# Sheet1_Young.net
KiCad netlist of a schematic drawn in Altium Designer
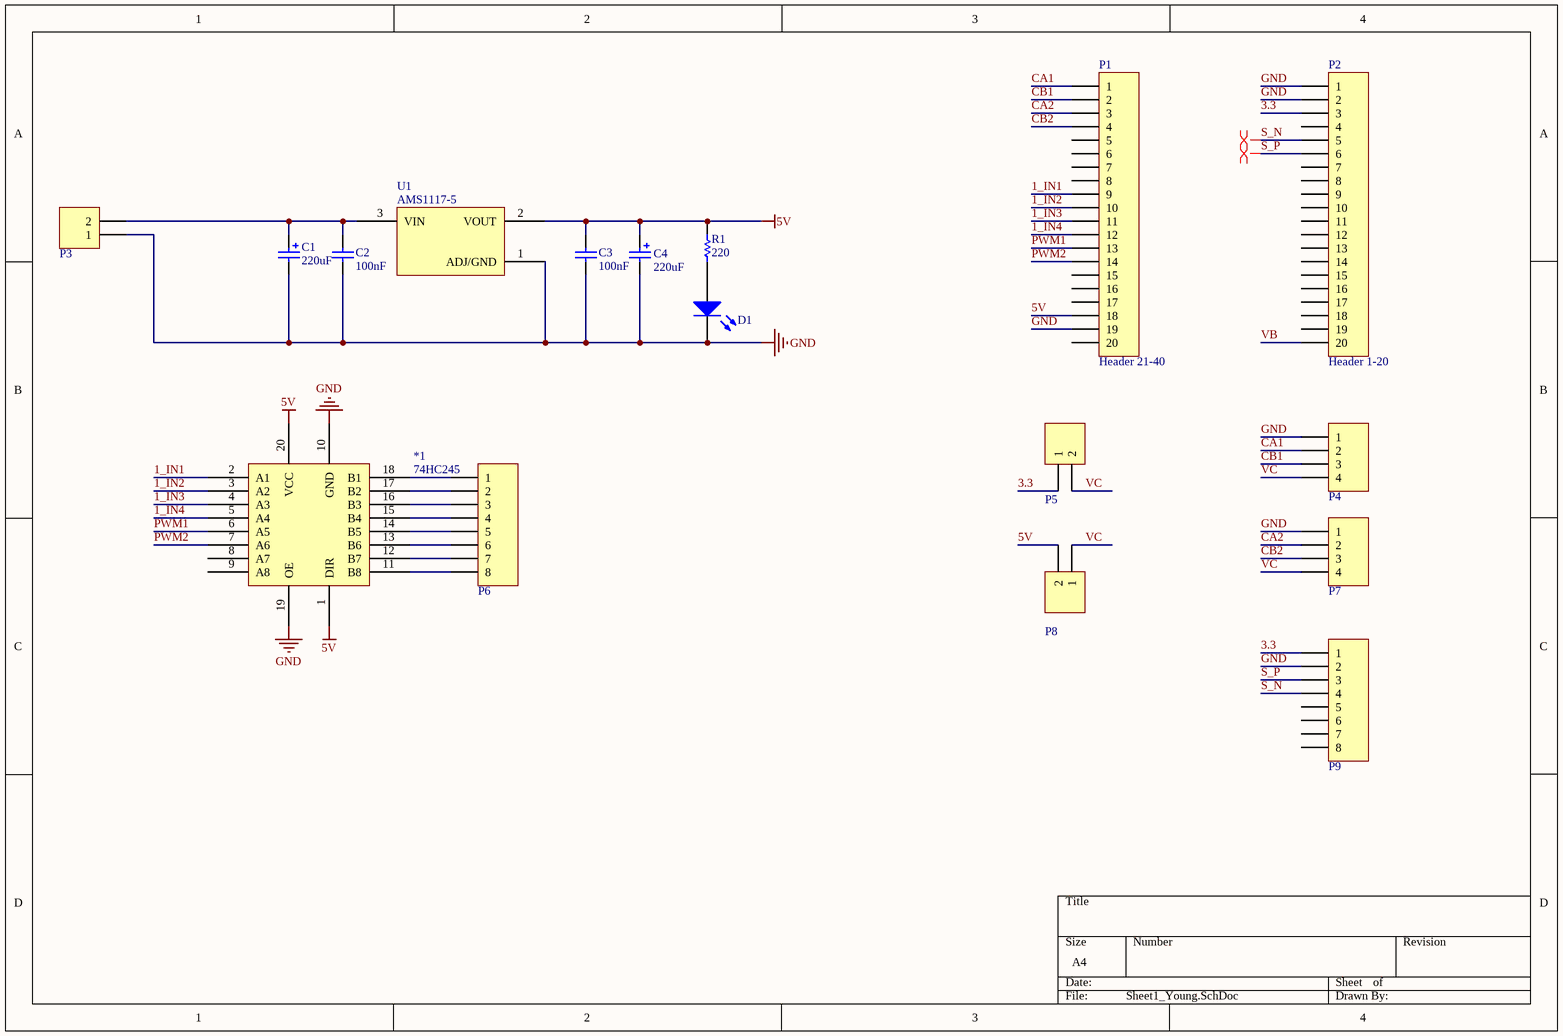
[diagram p0: Sheet1_Young.SchDoc]

(export (version "E")
  (design (tool "Eeschema 10.0.6"))
  (components
    (comp (ref "*1")
      (value "74HC245")
      (footprint "TSOP65P630X120-20N")
      (libsource (lib "Bus Transceiver") (part "74HC245"))
    )
    (comp (ref "C1")
      (value "220uF")
      (footprint "CAP ALU SIZE B")
      (description "Polarized Capacitor (Radial)")
      (fields (field (name "Comment") "Cap Pol SMD"))
      (libsource (lib "PIF_Library") (part "Cap Pol SMD"))
    )
    (comp (ref "C2")
      (value "100nF")
      (footprint "CAP-SM-0805")
      (description "Capacitor")
      (fields (field (name "Comment") "Cap Non-Pol SMD"))
      (libsource (lib "PIF_Library") (part "Cap Non-Pol SMD"))
    )
    (comp (ref "C3")
      (value "100nF")
      (footprint "CAP-SM-0805")
      (description "Capacitor")
      (fields (field (name "Comment") "Cap Non-Pol SMD"))
      (libsource (lib "PIF_Library") (part "Cap Non-Pol SMD"))
    )
    (comp (ref "C4")
      (value "220uF")
      (footprint "CAP ALU SIZE B")
      (description "Polarized Capacitor (Radial)")
      (fields (field (name "Comment") "Cap Pol SMD"))
      (libsource (lib "PIF_Library") (part "Cap Pol SMD"))
    )
    (comp (ref "D1")
      (value "LED SMD")
      (footprint "LED_0805_Blue")
      (description "LED")
      (libsource (lib "PIF_Library") (part "LED SMD"))
    )
    (comp (ref "P1")
      (value "Header 21-40")
      (footprint "HDR1X20")
      (description "Header, 20-Pin")
      (fields (field (name "PUBLISHER") "Altium Limited"))
      (libsource (lib "Miscellaneous Connectors") (part "Header 20"))
    )
    (comp (ref "P2")
      (value "Header 1-20")
      (footprint "HDR1X20")
      (description "Header, 20-Pin")
      (fields (field (name "PUBLISHER") "Altium Limited"))
      (libsource (lib "Miscellaneous Connectors") (part "Header 20"))
    )
    (comp (ref "P3")
      (value "Header 2")
      (footprint "JP2")
      (description "Header, 2-Pin")
      (fields (field (name "PUBLISHER") "Altium Limited"))
      (libsource (lib "") (part "Header 2_2"))
    )
    (comp (ref "P4")
      (value "Header 4")
      (footprint "JP4")
      (description "Header, 4-Pin")
      (fields (field (name "PUBLISHER") "Altium Limited"))
      (libsource (lib "PIF_Library") (part "Header 4"))
    )
    (comp (ref "P5")
      (value "Header 2")
      (footprint "JP2")
      (description "Header, 2-Pin")
      (fields (field (name "PUBLISHER") "Altium Limited"))
      (libsource (lib "") (part "Header 2_1"))
    )
    (comp (ref "P6")
      (value "Header 8")
      (footprint "JP8")
      (description "Header, 8-Pin")
      (fields (field (name "PUBLISHER") "Altium Limited"))
      (libsource (lib "PIF_Library") (part "Header 8"))
    )
    (comp (ref "P7")
      (value "Header 4")
      (footprint "JP4")
      (description "Header, 4-Pin")
      (fields (field (name "PUBLISHER") "Altium Limited"))
      (libsource (lib "PIF_Library") (part "Header 4"))
    )
    (comp (ref "P8")
      (value "Header 2")
      (footprint "JP2")
      (description "Header, 2-Pin")
      (fields (field (name "PUBLISHER") "Altium Limited"))
      (libsource (lib "PIF_Library") (part "Header 2"))
    )
    (comp (ref "P9")
      (value "Header 8")
      (footprint "JP8")
      (description "Header, 8-Pin")
      (fields (field (name "PUBLISHER") "Altium Limited"))
      (libsource (lib "PIF_Library") (part "Header 8"))
    )
    (comp (ref "R1")
      (value "220")
      (footprint "RES-SM-0805")
      (description "Resistor")
      (fields (field (name "Comment") "RESISTOR SMD"))
      (libsource (lib "PIF_Library") (part "RESISTOR SMD"))
    )
    (comp (ref "U1")
      (value "AMS1117-5")
      (footprint "SOT230P700X180-4N")
      (fields (field (name "MP") "AMS1117-3.3") (field (name "MF") "NEC"))
      (libsource (lib "AMS1117-3.3") (part "AMS1117-3.3"))
    )
  )
  (nets
    (net (code "1") (name "/1_IN1") (class "Default")
      (node (ref "*1") (pin "2") (pinfunction "A1_2") (pintype "passive"))
      (node (ref "P1") (pin "9") (pinfunction "9_9") (pintype "passive"))
    )
    (net (code "2") (name "/1_IN2") (class "Default")
      (node (ref "*1") (pin "3") (pinfunction "A2_3") (pintype "passive"))
      (node (ref "P1") (pin "10") (pinfunction "10_10") (pintype "passive"))
    )
    (net (code "3") (name "/1_IN3") (class "Default")
      (node (ref "*1") (pin "4") (pinfunction "A3_4") (pintype "passive"))
      (node (ref "P1") (pin "11") (pinfunction "11_11") (pintype "passive"))
    )
    (net (code "4") (name "/1_IN4") (class "Default")
      (node (ref "*1") (pin "5") (pinfunction "A4_5") (pintype "passive"))
      (node (ref "P1") (pin "12") (pinfunction "12_12") (pintype "passive"))
    )
    (net (code "5") (name "/3.3") (class "Default")
      (node (ref "P2") (pin "3") (pinfunction "3_3") (pintype "passive"))
      (node (ref "P5") (pin "1") (pinfunction "1_1") (pintype "passive"))
      (node (ref "P9") (pin "1") (pinfunction "1_1") (pintype "passive"))
    )
    (net (code "6") (name "/CA1") (class "Default")
      (node (ref "P1") (pin "1") (pinfunction "1_1") (pintype "passive"))
      (node (ref "P4") (pin "2") (pinfunction "2_2") (pintype "passive"))
    )
    (net (code "7") (name "/CA2") (class "Default")
      (node (ref "P1") (pin "3") (pinfunction "3_3") (pintype "passive"))
      (node (ref "P7") (pin "2") (pinfunction "2_2") (pintype "passive"))
    )
    (net (code "8") (name "/CB1") (class "Default")
      (node (ref "P1") (pin "2") (pinfunction "2_2") (pintype "passive"))
      (node (ref "P4") (pin "3") (pinfunction "3_3") (pintype "passive"))
    )
    (net (code "9") (name "/CB2") (class "Default")
      (node (ref "P1") (pin "4") (pinfunction "4_4") (pintype "passive"))
      (node (ref "P7") (pin "3") (pinfunction "3_3") (pintype "passive"))
    )
    (net (code "10") (name "/PWM1") (class "Default")
      (node (ref "*1") (pin "6") (pinfunction "A5_6") (pintype "passive"))
      (node (ref "P1") (pin "13") (pinfunction "13_13") (pintype "passive"))
    )
    (net (code "11") (name "/PWM2") (class "Default")
      (node (ref "*1") (pin "7") (pinfunction "A6_7") (pintype "passive"))
      (node (ref "P1") (pin "14") (pinfunction "14_14") (pintype "passive"))
    )
    (net (code "12") (name "/S_N") (class "Default")
      (node (ref "P2") (pin "5") (pinfunction "5_5") (pintype "passive"))
      (node (ref "P9") (pin "4") (pinfunction "4_4") (pintype "passive"))
    )
    (net (code "13") (name "/S_P") (class "Default")
      (node (ref "P2") (pin "6") (pinfunction "6_6") (pintype "passive"))
      (node (ref "P9") (pin "3") (pinfunction "3_3") (pintype "passive"))
    )
    (net (code "14") (name "/VB") (class "Default")
      (node (ref "P2") (pin "20") (pinfunction "20_20") (pintype "passive"))
    )
    (net (code "15") (name "/VC") (class "Default")
      (node (ref "P4") (pin "4") (pinfunction "4_4") (pintype "passive"))
      (node (ref "P5") (pin "2") (pinfunction "2_2") (pintype "passive"))
      (node (ref "P7") (pin "4") (pinfunction "4_4") (pintype "passive"))
      (node (ref "P8") (pin "1") (pinfunction "1_1") (pintype "passive"))
    )
    (net (code "16") (name "5V") (class "Default")
      (node (ref "*1") (pin "1") (pinfunction "DIR_1") (pintype "passive"))
      (node (ref "*1") (pin "20") (pinfunction "VCC_20") (pintype "passive"))
      (node (ref "C3") (pin "1") (pinfunction "1_1") (pintype "passive"))
      (node (ref "C4") (pin "1") (pinfunction "1_1") (pintype "passive"))
      (node (ref "P1") (pin "18") (pinfunction "18_18") (pintype "passive"))
      (node (ref "P8") (pin "2") (pinfunction "2_2") (pintype "passive"))
      (node (ref "R1") (pin "2") (pinfunction "2_2") (pintype "passive"))
      (node (ref "U1") (pin "2") (pinfunction "VOUT_2") (pintype "passive"))
    )
    (net (code "17") (name "GND") (class "Default")
      (node (ref "*1") (pin "10") (pinfunction "GND_10") (pintype "passive"))
      (node (ref "*1") (pin "19") (pinfunction "OE_19") (pintype "passive"))
      (node (ref "C1") (pin "2") (pinfunction "2_2") (pintype "passive"))
      (node (ref "C2") (pin "1") (pinfunction "1_1") (pintype "passive"))
      (node (ref "C3") (pin "2") (pinfunction "2_2") (pintype "passive"))
      (node (ref "C4") (pin "2") (pinfunction "2_2") (pintype "passive"))
      (node (ref "D1") (pin "2") (pinfunction "K_2") (pintype "passive"))
      (node (ref "P1") (pin "19") (pinfunction "19_19") (pintype "passive"))
      (node (ref "P2") (pin "1") (pinfunction "1_1") (pintype "passive"))
      (node (ref "P2") (pin "2") (pinfunction "2_2") (pintype "passive"))
      (node (ref "P3") (pin "1") (pinfunction "1_1") (pintype "passive"))
      (node (ref "P4") (pin "1") (pinfunction "1_1") (pintype "passive"))
      (node (ref "P7") (pin "1") (pinfunction "1_1") (pintype "passive"))
      (node (ref "P9") (pin "2") (pinfunction "2_2") (pintype "passive"))
      (node (ref "U1") (pin "1") (pinfunction "ADJ/GND_1") (pintype "passive"))
    )
    (net (code "18") (name "Net-(*1-B1)") (class "Default")
      (node (ref "*1") (pin "18") (pinfunction "B1_18") (pintype "passive"))
      (node (ref "P6") (pin "1") (pinfunction "1_1") (pintype "passive"))
    )
    (net (code "19") (name "Net-(*1-B2)") (class "Default")
      (node (ref "*1") (pin "17") (pinfunction "B2_17") (pintype "passive"))
      (node (ref "P6") (pin "2") (pinfunction "2_2") (pintype "passive"))
    )
    (net (code "20") (name "Net-(*1-B3)") (class "Default")
      (node (ref "*1") (pin "16") (pinfunction "B3_16") (pintype "passive"))
      (node (ref "P6") (pin "3") (pinfunction "3_3") (pintype "passive"))
    )
    (net (code "21") (name "Net-(*1-B4)") (class "Default")
      (node (ref "*1") (pin "15") (pinfunction "B4_15") (pintype "passive"))
      (node (ref "P6") (pin "4") (pinfunction "4_4") (pintype "passive"))
    )
    (net (code "22") (name "Net-(*1-B5)") (class "Default")
      (node (ref "*1") (pin "14") (pinfunction "B5_14") (pintype "passive"))
      (node (ref "P6") (pin "5") (pinfunction "5_5") (pintype "passive"))
    )
    (net (code "23") (name "Net-(*1-B6)") (class "Default")
      (node (ref "*1") (pin "13") (pinfunction "B6_13") (pintype "passive"))
      (node (ref "P6") (pin "6") (pinfunction "6_6") (pintype "passive"))
    )
    (net (code "24") (name "Net-(*1-B7)") (class "Default")
      (node (ref "*1") (pin "12") (pinfunction "B7_12") (pintype "passive"))
      (node (ref "P6") (pin "7") (pinfunction "7_7") (pintype "passive"))
    )
    (net (code "25") (name "Net-(*1-B8)") (class "Default")
      (node (ref "*1") (pin "11") (pinfunction "B8_11") (pintype "passive"))
      (node (ref "P6") (pin "8") (pinfunction "8_8") (pintype "passive"))
    )
    (net (code "26") (name "Net-(D1-A)") (class "Default")
      (node (ref "D1") (pin "1") (pinfunction "A_1") (pintype "passive"))
      (node (ref "R1") (pin "1") (pinfunction "1_1") (pintype "passive"))
    )
    (net (code "27") (name "Net-(U1-VIN)") (class "Default")
      (node (ref "C1") (pin "1") (pinfunction "1_1") (pintype "passive"))
      (node (ref "C2") (pin "2") (pinfunction "2_2") (pintype "passive"))
      (node (ref "P3") (pin "2") (pinfunction "2_2") (pintype "passive"))
      (node (ref "U1") (pin "3") (pinfunction "VIN_3") (pintype "passive"))
    )
    (net (code "28") (name "unconnected-(*1-A7-Pad8)") (class "Default")
      (node (ref "*1") (pin "8") (pinfunction "A7_8") (pintype "passive"))
    )
    (net (code "29") (name "unconnected-(*1-A8-Pad9)") (class "Default")
      (node (ref "*1") (pin "9") (pinfunction "A8_9") (pintype "passive"))
    )
    (net (code "30") (name "unconnected-(P1-Pad5)") (class "Default")
      (node (ref "P1") (pin "5") (pinfunction "5_5") (pintype "passive"))
    )
    (net (code "31") (name "unconnected-(P1-Pad6)") (class "Default")
      (node (ref "P1") (pin "6") (pinfunction "6_6") (pintype "passive"))
    )
    (net (code "32") (name "unconnected-(P1-Pad7)") (class "Default")
      (node (ref "P1") (pin "7") (pinfunction "7_7") (pintype "passive"))
    )
    (net (code "33") (name "unconnected-(P1-Pad8)") (class "Default")
      (node (ref "P1") (pin "8") (pinfunction "8_8") (pintype "passive"))
    )
    (net (code "34") (name "unconnected-(P1-Pad15)") (class "Default")
      (node (ref "P1") (pin "15") (pinfunction "15_15") (pintype "passive"))
    )
    (net (code "35") (name "unconnected-(P1-Pad16)") (class "Default")
      (node (ref "P1") (pin "16") (pinfunction "16_16") (pintype "passive"))
    )
    (net (code "36") (name "unconnected-(P1-Pad17)") (class "Default")
      (node (ref "P1") (pin "17") (pinfunction "17_17") (pintype "passive"))
    )
    (net (code "37") (name "unconnected-(P1-Pad20)") (class "Default")
      (node (ref "P1") (pin "20") (pinfunction "20_20") (pintype "passive"))
    )
    (net (code "38") (name "unconnected-(P2-Pad4)") (class "Default")
      (node (ref "P2") (pin "4") (pinfunction "4_4") (pintype "passive"))
    )
    (net (code "39") (name "unconnected-(P2-Pad7)") (class "Default")
      (node (ref "P2") (pin "7") (pinfunction "7_7") (pintype "passive"))
    )
    (net (code "40") (name "unconnected-(P2-Pad8)") (class "Default")
      (node (ref "P2") (pin "8") (pinfunction "8_8") (pintype "passive"))
    )
    (net (code "41") (name "unconnected-(P2-Pad9)") (class "Default")
      (node (ref "P2") (pin "9") (pinfunction "9_9") (pintype "passive"))
    )
    (net (code "42") (name "unconnected-(P2-Pad10)") (class "Default")
      (node (ref "P2") (pin "10") (pinfunction "10_10") (pintype "passive"))
    )
    (net (code "43") (name "unconnected-(P2-Pad11)") (class "Default")
      (node (ref "P2") (pin "11") (pinfunction "11_11") (pintype "passive"))
    )
    (net (code "44") (name "unconnected-(P2-Pad12)") (class "Default")
      (node (ref "P2") (pin "12") (pinfunction "12_12") (pintype "passive"))
    )
    (net (code "45") (name "unconnected-(P2-Pad13)") (class "Default")
      (node (ref "P2") (pin "13") (pinfunction "13_13") (pintype "passive"))
    )
    (net (code "46") (name "unconnected-(P2-Pad14)") (class "Default")
      (node (ref "P2") (pin "14") (pinfunction "14_14") (pintype "passive"))
    )
    (net (code "47") (name "unconnected-(P2-Pad15)") (class "Default")
      (node (ref "P2") (pin "15") (pinfunction "15_15") (pintype "passive"))
    )
    (net (code "48") (name "unconnected-(P2-Pad16)") (class "Default")
      (node (ref "P2") (pin "16") (pinfunction "16_16") (pintype "passive"))
    )
    (net (code "49") (name "unconnected-(P2-Pad17)") (class "Default")
      (node (ref "P2") (pin "17") (pinfunction "17_17") (pintype "passive"))
    )
    (net (code "50") (name "unconnected-(P2-Pad18)") (class "Default")
      (node (ref "P2") (pin "18") (pinfunction "18_18") (pintype "passive"))
    )
    (net (code "51") (name "unconnected-(P2-Pad19)") (class "Default")
      (node (ref "P2") (pin "19") (pinfunction "19_19") (pintype "passive"))
    )
    (net (code "52") (name "unconnected-(P9-Pad5)") (class "Default")
      (node (ref "P9") (pin "5") (pinfunction "5_5") (pintype "passive"))
    )
    (net (code "53") (name "unconnected-(P9-Pad6)") (class "Default")
      (node (ref "P9") (pin "6") (pinfunction "6_6") (pintype "passive"))
    )
    (net (code "54") (name "unconnected-(P9-Pad7)") (class "Default")
      (node (ref "P9") (pin "7") (pinfunction "7_7") (pintype "passive"))
    )
    (net (code "55") (name "unconnected-(P9-Pad8)") (class "Default")
      (node (ref "P9") (pin "8") (pinfunction "8_8") (pintype "passive"))
    )
  )
)
